# 04_SWITCH.net
KiCad netlist of a schematic drawn in Altium Designer
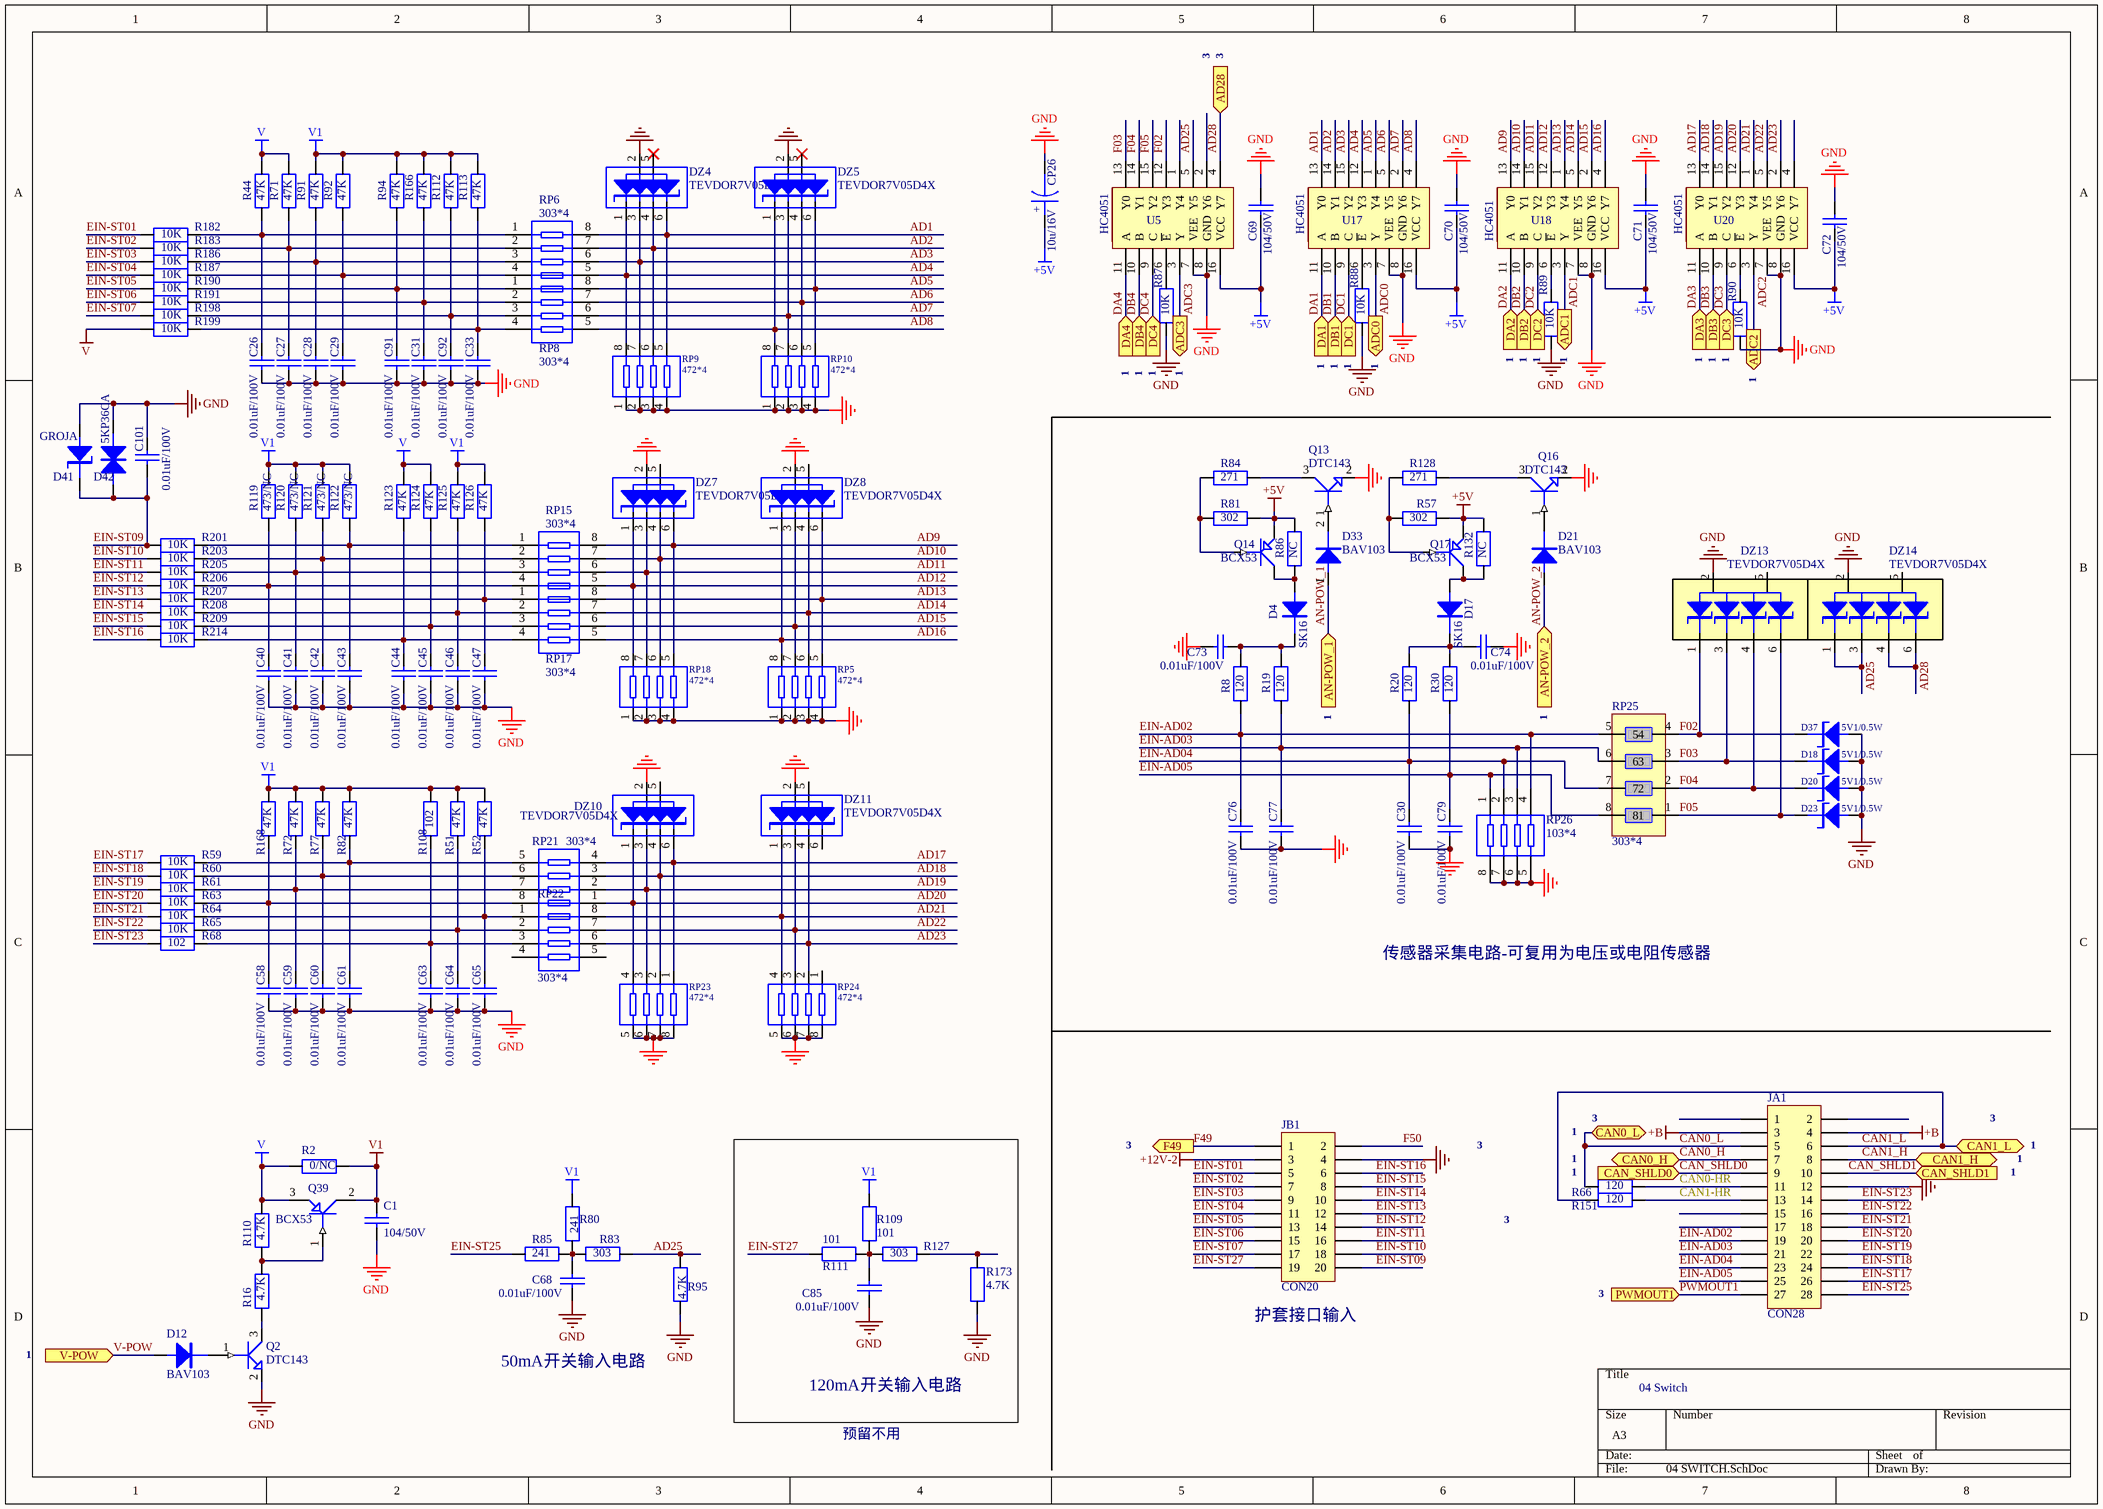
[diagram p0: 04 SWITCH.SchDoc]

(export (version "E")
  (design (tool "Eeschema 10.0.6"))
  (components
    (comp (ref "C1")
      (value "104/50V")
      (footprint "CR0805")
      (description "贴片电容")
      (libsource (lib "*") (part "CAP"))
    )
    (comp (ref "C26")
      (value "0.01uF/100V")
      (footprint "CR0805")
      (description "Capacitor")
      (libsource (lib "*") (part "CAP"))
    )
    (comp (ref "C27")
      (value "0.01uF/100V")
      (footprint "CR0805")
      (description "Capacitor")
      (libsource (lib "*") (part "CAP"))
    )
    (comp (ref "C28")
      (value "0.01uF/100V")
      (footprint "CR0805")
      (description "Capacitor")
      (libsource (lib "*") (part "CAP"))
    )
    (comp (ref "C29")
      (value "0.01uF/100V")
      (footprint "CR0805")
      (description "Capacitor")
      (libsource (lib "*") (part "CAP"))
    )
    (comp (ref "C30")
      (value "0.01uF/100V")
      (footprint "CR0805")
      (description "Capacitor")
      (libsource (lib "*") (part "CAP"))
    )
    (comp (ref "C31")
      (value "0.01uF/100V")
      (footprint "CR0805")
      (description "Capacitor")
      (libsource (lib "*") (part "CAP"))
    )
    (comp (ref "C33")
      (value "0.01uF/100V")
      (footprint "CR0805")
      (description "Capacitor")
      (libsource (lib "*") (part "CAP"))
    )
    (comp (ref "C40")
      (value "0.01uF/100V")
      (footprint "CR0805")
      (description "Capacitor")
      (libsource (lib "*") (part "CAP"))
    )
    (comp (ref "C41")
      (value "0.01uF/100V")
      (footprint "CR0805")
      (description "Capacitor")
      (libsource (lib "*") (part "CAP"))
    )
    (comp (ref "C42")
      (value "0.01uF/100V")
      (footprint "CR0805")
      (description "Capacitor")
      (libsource (lib "*") (part "CAP"))
    )
    (comp (ref "C43")
      (value "0.01uF/100V")
      (footprint "CR0805")
      (description "Capacitor")
      (libsource (lib "*") (part "CAP"))
    )
    (comp (ref "C44")
      (value "0.01uF/100V")
      (footprint "CR0805")
      (description "Capacitor")
      (libsource (lib "*") (part "CAP"))
    )
    (comp (ref "C45")
      (value "0.01uF/100V")
      (footprint "CR0805")
      (description "Capacitor")
      (libsource (lib "*") (part "CAP"))
    )
    (comp (ref "C46")
      (value "0.01uF/100V")
      (footprint "CR0805")
      (description "Capacitor")
      (libsource (lib "*") (part "CAP"))
    )
    (comp (ref "C47")
      (value "0.01uF/100V")
      (footprint "CR0805")
      (description "Capacitor")
      (libsource (lib "*") (part "CAP"))
    )
    (comp (ref "C58")
      (value "0.01uF/100V")
      (footprint "CR0805")
      (description "Capacitor")
      (libsource (lib "*") (part "CAP"))
    )
    (comp (ref "C59")
      (value "0.01uF/100V")
      (footprint "CR0805")
      (description "Capacitor")
      (libsource (lib "*") (part "CAP"))
    )
    (comp (ref "C60")
      (value "0.01uF/100V")
      (footprint "CR0805")
      (description "Capacitor")
      (libsource (lib "*") (part "CAP"))
    )
    (comp (ref "C61")
      (value "0.01uF/100V")
      (footprint "CR0805")
      (description "Capacitor")
      (libsource (lib "*") (part "CAP"))
    )
    (comp (ref "C63")
      (value "0.01uF/100V")
      (footprint "CR0805")
      (description "Capacitor")
      (libsource (lib "*") (part "CAP"))
    )
    (comp (ref "C64")
      (value "0.01uF/100V")
      (footprint "CR0805")
      (description "Capacitor")
      (libsource (lib "*") (part "CAP"))
    )
    (comp (ref "C65")
      (value "0.01uF/100V")
      (footprint "CR0805")
      (description "Capacitor")
      (libsource (lib "*") (part "CAP"))
    )
    (comp (ref "C68")
      (value "0.01uF/100V")
      (footprint "CR0805")
      (description "Capacitor")
      (libsource (lib "*") (part "CAP"))
    )
    (comp (ref "C69")
      (value "104/50V")
      (footprint "CR0805")
      (description "Capacitor")
      (libsource (lib "*") (part "CAP"))
    )
    (comp (ref "C70")
      (value "104/50V")
      (footprint "CR0805")
      (description "Capacitor")
      (libsource (lib "*") (part "CAP"))
    )
    (comp (ref "C71")
      (value "104/50V")
      (footprint "CR0805")
      (description "Capacitor")
      (libsource (lib "*") (part "CAP"))
    )
    (comp (ref "C72")
      (value "104/50V")
      (footprint "CR0805")
      (description "Capacitor")
      (libsource (lib "*") (part "CAP"))
    )
    (comp (ref "C73")
      (value "0.01uF/100V")
      (footprint "CR0805")
      (description "Capacitor")
      (libsource (lib "*") (part "CAP"))
    )
    (comp (ref "C74")
      (value "0.01uF/100V")
      (footprint "CR0805")
      (description "Capacitor")
      (libsource (lib "*") (part "CAP"))
    )
    (comp (ref "C76")
      (value "0.01uF/100V")
      (footprint "CR0805")
      (description "Capacitor")
      (libsource (lib "*") (part "CAP"))
    )
    (comp (ref "C77")
      (value "0.01uF/100V")
      (footprint "CR0805")
      (description "Capacitor")
      (libsource (lib "*") (part "CAP"))
    )
    (comp (ref "C79")
      (value "0.01uF/100V")
      (footprint "CR0805")
      (description "Capacitor")
      (libsource (lib "*") (part "CAP"))
    )
    (comp (ref "C85")
      (value "0.01uF/100V")
      (footprint "CR0805")
      (description "Capacitor")
      (libsource (lib "*") (part "CAP"))
    )
    (comp (ref "C91")
      (value "0.01uF/100V")
      (footprint "CR0805")
      (description "Capacitor")
      (libsource (lib "*") (part "CAP"))
    )
    (comp (ref "C92")
      (value "0.01uF/100V")
      (footprint "CR0805")
      (description "Capacitor")
      (libsource (lib "*") (part "CAP"))
    )
    (comp (ref "C101")
      (value "0.01uF/100V")
      (footprint "CR0805")
      (description "Capacitor")
      (libsource (lib "*") (part "CAP"))
    )
    (comp (ref "CP26")
      (value "10u/16V")
      (footprint "CE1206")
      (description "Capacitor")
      (libsource (lib "*") (part "CAPACITOR POL"))
    )
    (comp (ref "D4")
      (value "SK16")
      (footprint "SMA")
      (description "二极管")
      (libsource (lib "*") (part "DIODE"))
    )
    (comp (ref "D12")
      (value "BAV103")
      (footprint "SOD-80C")
      (description "二极管")
      (libsource (lib "*") (part "DIODE"))
    )
    (comp (ref "D17")
      (value "SK16")
      (footprint "SMA")
      (description "二极管")
      (libsource (lib "*") (part "DIODE"))
    )
    (comp (ref "D18")
      (value "5V1/0.5W")
      (footprint "SOD-80C")
      (description "稳压二极管")
      (libsource (lib "*") (part "DW"))
    )
    (comp (ref "D20")
      (value "5V1/0.5W")
      (footprint "SOD-80C")
      (description "稳压二极管")
      (libsource (lib "*") (part "DW"))
    )
    (comp (ref "D21")
      (value "BAV103")
      (footprint "SOD-80C")
      (description "二极管")
      (libsource (lib "*") (part "DIODE"))
    )
    (comp (ref "D23")
      (value "5V1/0.5W")
      (footprint "SOD-80C")
      (description "稳压二极管")
      (libsource (lib "*") (part "DW"))
    )
    (comp (ref "D33")
      (value "BAV103")
      (footprint "SOD-80C")
      (description "二极管")
      (libsource (lib "") (part "DIODE_1"))
    )
    (comp (ref "D37")
      (value "5V1/0.5W")
      (footprint "SOD-80C")
      (description "稳压二极管")
      (libsource (lib "*") (part "DW"))
    )
    (comp (ref "D41")
      (value "GROJA")
      (footprint "SMA")
      (description "稳压二极管")
      (libsource (lib "*") (part "DW"))
    )
    (comp (ref "D42") (value "5KP36CA") (footprint "SMB-D") (libsource (lib "*") (part "TVS")))
    (comp (ref "DZ4")
      (value "TEVDOR7V05D4X")
      (footprint "SOT-457")
      (description "二极管排")
      (libsource (lib "yibiaoschlib") (part "TEVDOR7V05D4X"))
    )
    (comp (ref "DZ5")
      (value "TEVDOR7V05D4X")
      (footprint "SOT-457")
      (description "二极管排")
      (libsource (lib "yibiaoschlib") (part "TEVDOR7V05D4X"))
    )
    (comp (ref "DZ7")
      (value "TEVDOR7V05D4X")
      (footprint "SOT-457")
      (description "二极管排")
      (libsource (lib "yibiaoschlib") (part "TEVDOR7V05D4X"))
    )
    (comp (ref "DZ8")
      (value "TEVDOR7V05D4X")
      (footprint "SOT-457")
      (description "二极管排")
      (libsource (lib "yibiaoschlib") (part "TEVDOR7V05D4X"))
    )
    (comp (ref "DZ10")
      (value "TEVDOR7V05D4X")
      (footprint "SOT-457")
      (description "二极管排")
      (libsource (lib "yibiaoschlib") (part "TEVDOR7V05D4X"))
    )
    (comp (ref "DZ11")
      (value "TEVDOR7V05D4X")
      (footprint "SOT-457")
      (description "二极管排")
      (libsource (lib "yibiaoschlib") (part "TEVDOR7V05D4X"))
    )
    (comp (ref "DZ13")
      (value "TEVDOR7V05D4X")
      (footprint "SOT-457")
      (description "二极管排")
      (libsource (lib "*") (part "TEVDOR7V05D4X"))
    )
    (comp (ref "DZ14")
      (value "TEVDOR7V05D4X")
      (footprint "SOT-457")
      (description "二极管排")
      (libsource (lib "*") (part "TEVDOR7V05D4X"))
    )
    (comp (ref "JA1") (value "CON28") (footprint "AMP DIP28") (libsource (lib "YDM-SQ-1SCH") (part "CON28")))
    (comp (ref "JB1") (value "CON20") (footprint "AMP DIP20") (libsource (lib "YDM-SQ-1SCH") (part "CON20")))
    (comp (ref "Q2")
      (value "DTC143")
      (footprint "SOT23")
      (description "NPN")
      (libsource (lib "Ô­ÀíÍ¼¿â-1SCH") (part "DTC143"))
    )
    (comp (ref "Q13")
      (value "DTC143")
      (footprint "SOT23")
      (description "NPN")
      (libsource (lib "Ô­ÀíÍ¼¿â-1SCH") (part "DTC143"))
    )
    (comp (ref "Q14")
      (value "BCX53")
      (footprint "SOT89")
      (description "贴片三极管")
      (libsource (lib "*") (part "PNP1"))
    )
    (comp (ref "Q16")
      (value "DTC143")
      (footprint "SOT23")
      (description "NPN")
      (libsource (lib "Ô­ÀíÍ¼¿â-1SCH") (part "DTC143"))
    )
    (comp (ref "Q17")
      (value "BCX53")
      (footprint "SOT89")
      (description "贴片三极管")
      (libsource (lib "*") (part "PNP1"))
    )
    (comp (ref "Q39")
      (value "BCX53")
      (footprint "SOT89")
      (description "PNP三极管")
      (libsource (lib "Ô­ÀíÍ¼¿â-1SCH") (part "BSP631"))
    )
    (comp (ref "R2")
      (value "0/NC")
      (footprint "CR1206")
      (description "贴片电阻")
      (libsource (lib "YDM-SQ-1SCH") (part "RES"))
    )
    (comp (ref "R8")
      (value "120")
      (footprint "CR1206")
      (description "贴片电阻")
      (libsource (lib "*") (part "RES"))
    )
    (comp (ref "R16")
      (value "4.7K")
      (footprint "CR1206")
      (description "贴片电阻")
      (libsource (lib "*") (part "RES"))
    )
    (comp (ref "R19")
      (value "120")
      (footprint "CR1206")
      (description "贴片电阻")
      (libsource (lib "*") (part "RES"))
    )
    (comp (ref "R20")
      (value "120")
      (footprint "CR1206")
      (description "贴片电阻")
      (libsource (lib "*") (part "RES"))
    )
    (comp (ref "R30")
      (value "120")
      (footprint "CR1206")
      (description "贴片电阻")
      (libsource (lib "*") (part "RES"))
    )
    (comp (ref "R44")
      (value "47K")
      (footprint "CR0805")
      (description "贴片电阻")
      (libsource (lib "*") (part "RES"))
    )
    (comp (ref "R51")
      (value "47K")
      (footprint "CR0805")
      (description "贴片电阻")
      (libsource (lib "*") (part "RES"))
    )
    (comp (ref "R52")
      (value "47K")
      (footprint "CR0805")
      (description "贴片电阻")
      (libsource (lib "*") (part "RES"))
    )
    (comp (ref "R57")
      (value "302")
      (footprint "CR0805")
      (description "贴片电阻")
      (libsource (lib "*") (part "RES"))
    )
    (comp (ref "R59")
      (value "10K")
      (footprint "CR1206")
      (description "贴片电阻")
      (libsource (lib "*") (part "RES"))
    )
    (comp (ref "R60")
      (value "10K")
      (footprint "CR1206")
      (description "贴片电阻")
      (libsource (lib "*") (part "RES"))
    )
    (comp (ref "R61")
      (value "10K")
      (footprint "CR1206")
      (description "贴片电阻")
      (libsource (lib "*") (part "RES"))
    )
    (comp (ref "R63")
      (value "10K")
      (footprint "CR1206")
      (description "贴片电阻")
      (libsource (lib "*") (part "RES"))
    )
    (comp (ref "R64")
      (value "10K")
      (footprint "CR1206")
      (description "贴片电阻")
      (libsource (lib "*") (part "RES"))
    )
    (comp (ref "R65")
      (value "10K")
      (footprint "CR1206")
      (description "贴片电阻")
      (libsource (lib "*") (part "RES"))
    )
    (comp (ref "R66")
      (value "120")
      (footprint "CR0805")
      (description "贴片电阻")
      (libsource (lib "*") (part "RES"))
    )
    (comp (ref "R68")
      (value "102")
      (footprint "CR2010")
      (description "贴片电阻")
      (libsource (lib "*") (part "RES"))
    )
    (comp (ref "R71")
      (value "47K")
      (footprint "CR0805")
      (description "贴片电阻")
      (libsource (lib "*") (part "RES"))
    )
    (comp (ref "R72")
      (value "47K")
      (footprint "CR0805")
      (description "贴片电阻")
      (libsource (lib "*") (part "RES"))
    )
    (comp (ref "R77")
      (value "47K")
      (footprint "CR0805")
      (description "贴片电阻")
      (libsource (lib "*") (part "RES"))
    )
    (comp (ref "R80")
      (value "241")
      (footprint "R-3W")
      (description "贴片电阻")
      (libsource (lib "*") (part "RES"))
    )
    (comp (ref "R81")
      (value "302")
      (footprint "CR0805")
      (description "贴片电阻")
      (libsource (lib "*") (part "RES"))
    )
    (comp (ref "R82")
      (value "47K")
      (footprint "CR0805")
      (description "贴片电阻")
      (libsource (lib "*") (part "RES"))
    )
    (comp (ref "R83")
      (value "303")
      (footprint "CR0805")
      (description "贴片电阻")
      (libsource (lib "*") (part "RES"))
    )
    (comp (ref "R84")
      (value "271")
      (footprint "CR0805")
      (description "贴片电阻")
      (libsource (lib "*") (part "RES"))
    )
    (comp (ref "R85")
      (value "241")
      (footprint "R-3W")
      (description "贴片电阻")
      (libsource (lib "*") (part "RES"))
    )
    (comp (ref "R86")
      (value "NC")
      (footprint "CR1206")
      (description "贴片电阻")
      (libsource (lib "*") (part "RES"))
    )
    (comp (ref "R87")
      (value "10K")
      (footprint "CR0805")
      (description "贴片电阻")
      (libsource (lib "*") (part "RES"))
    )
    (comp (ref "R88")
      (value "10K")
      (footprint "CR0805")
      (description "贴片电阻")
      (libsource (lib "*") (part "RES"))
    )
    (comp (ref "R89")
      (value "10K")
      (footprint "CR0805")
      (description "贴片电阻")
      (libsource (lib "*") (part "RES"))
    )
    (comp (ref "R90")
      (value "10K")
      (footprint "CR0805")
      (description "贴片电阻")
      (libsource (lib "*") (part "RES"))
    )
    (comp (ref "R91")
      (value "47K")
      (footprint "CR0805")
      (description "贴片电阻")
      (libsource (lib "*") (part "RES"))
    )
    (comp (ref "R92")
      (value "47K")
      (footprint "CR0805")
      (description "贴片电阻")
      (libsource (lib "*") (part "RES"))
    )
    (comp (ref "R94")
      (value "47K")
      (footprint "CR0805")
      (description "贴片电阻")
      (libsource (lib "*") (part "RES"))
    )
    (comp (ref "R95")
      (value "4.7K")
      (footprint "CR0805")
      (description "贴片电阻")
      (libsource (lib "*") (part "RES"))
    )
    (comp (ref "R108")
      (value "102")
      (footprint "CR2010")
      (description "贴片电阻")
      (libsource (lib "*") (part "RES"))
    )
    (comp (ref "R109")
      (value "101")
      (footprint "R-3W")
      (description "贴片电阻")
      (libsource (lib "*") (part "RES"))
    )
    (comp (ref "R110")
      (value "4.7K")
      (footprint "CR0805")
      (description "贴片电阻")
      (libsource (lib "*") (part "RES"))
    )
    (comp (ref "R111")
      (value "101")
      (footprint "R-3W")
      (description "贴片电阻")
      (libsource (lib "*") (part "RES"))
    )
    (comp (ref "R112")
      (value "47K")
      (footprint "CR0805")
      (description "贴片电阻")
      (libsource (lib "*") (part "RES"))
    )
    (comp (ref "R113")
      (value "47K")
      (footprint "CR0805")
      (description "贴片电阻")
      (libsource (lib "*") (part "RES"))
    )
    (comp (ref "R119")
      (value "473/NC")
      (footprint "CR0805")
      (description "贴片电阻")
      (libsource (lib "*") (part "RES"))
    )
    (comp (ref "R120")
      (value "473/NC")
      (footprint "CR0805")
      (description "贴片电阻")
      (libsource (lib "*") (part "RES"))
    )
    (comp (ref "R121")
      (value "473/NC")
      (footprint "CR0805")
      (description "贴片电阻")
      (libsource (lib "*") (part "RES"))
    )
    (comp (ref "R122")
      (value "473/NC")
      (footprint "CR0805")
      (description "贴片电阻")
      (libsource (lib "*") (part "RES"))
    )
    (comp (ref "R123")
      (value "47K")
      (footprint "CR0805")
      (description "贴片电阻")
      (libsource (lib "*") (part "RES"))
    )
    (comp (ref "R124")
      (value "47K")
      (footprint "CR0805")
      (description "贴片电阻")
      (libsource (lib "*") (part "RES"))
    )
    (comp (ref "R125")
      (value "47K")
      (footprint "CR0805")
      (description "贴片电阻")
      (libsource (lib "*") (part "RES"))
    )
    (comp (ref "R126")
      (value "47K")
      (footprint "CR0805")
      (description "贴片电阻")
      (libsource (lib "*") (part "RES"))
    )
    (comp (ref "R127")
      (value "303")
      (footprint "CR0805")
      (description "贴片电阻")
      (libsource (lib "*") (part "RES"))
    )
    (comp (ref "R128")
      (value "271")
      (footprint "CR0805")
      (description "贴片电阻")
      (libsource (lib "*") (part "RES"))
    )
    (comp (ref "R132")
      (value "NC")
      (footprint "CR1206")
      (description "贴片电阻")
      (libsource (lib "*") (part "RES"))
    )
    (comp (ref "R151")
      (value "120")
      (footprint "CR0805")
      (description "贴片电阻")
      (libsource (lib "*") (part "RES"))
    )
    (comp (ref "R166")
      (value "47K")
      (footprint "CR0805")
      (description "贴片电阻")
      (libsource (lib "*") (part "RES"))
    )
    (comp (ref "R168")
      (value "47K")
      (footprint "CR0805")
      (description "贴片电阻")
      (libsource (lib "*") (part "RES"))
    )
    (comp (ref "R173")
      (value "4.7K")
      (footprint "CR0805")
      (description "贴片电阻")
      (libsource (lib "*") (part "RES"))
    )
    (comp (ref "R182")
      (value "10K")
      (footprint "CR1206")
      (description "贴片电阻")
      (libsource (lib "*") (part "RES"))
    )
    (comp (ref "R183")
      (value "10K")
      (footprint "CR1206")
      (description "贴片电阻")
      (libsource (lib "*") (part "RES"))
    )
    (comp (ref "R186")
      (value "10K")
      (footprint "CR1206")
      (description "贴片电阻")
      (libsource (lib "*") (part "RES"))
    )
    (comp (ref "R187")
      (value "10K")
      (footprint "CR1206")
      (description "贴片电阻")
      (libsource (lib "*") (part "RES"))
    )
    (comp (ref "R190")
      (value "10K")
      (footprint "CR1206")
      (description "贴片电阻")
      (libsource (lib "*") (part "RES"))
    )
    (comp (ref "R191")
      (value "10K")
      (footprint "CR1206")
      (description "贴片电阻")
      (libsource (lib "*") (part "RES"))
    )
    (comp (ref "R198")
      (value "10K")
      (footprint "CR1206")
      (description "贴片电阻")
      (libsource (lib "*") (part "RES"))
    )
    (comp (ref "R199")
      (value "10K")
      (footprint "CR1206")
      (description "贴片电阻")
      (libsource (lib "*") (part "RES"))
    )
    (comp (ref "R201")
      (value "10K")
      (footprint "CR1206")
      (description "贴片电阻")
      (libsource (lib "*") (part "RES"))
    )
    (comp (ref "R203")
      (value "10K")
      (footprint "CR1206")
      (description "贴片电阻")
      (libsource (lib "*") (part "RES"))
    )
    (comp (ref "R205")
      (value "10K")
      (footprint "CR1206")
      (description "贴片电阻")
      (libsource (lib "*") (part "RES"))
    )
    (comp (ref "R206")
      (value "10K")
      (footprint "CR1206")
      (description "贴片电阻")
      (libsource (lib "*") (part "RES"))
    )
    (comp (ref "R207")
      (value "10K")
      (footprint "CR1206")
      (description "贴片电阻")
      (libsource (lib "*") (part "RES"))
    )
    (comp (ref "R208")
      (value "10K")
      (footprint "CR1206")
      (description "贴片电阻")
      (libsource (lib "*") (part "RES"))
    )
    (comp (ref "R209")
      (value "10K")
      (footprint "CR1206")
      (description "贴片电阻")
      (libsource (lib "*") (part "RES"))
    )
    (comp (ref "R214")
      (value "10K")
      (footprint "CR1206")
      (description "贴片电阻")
      (libsource (lib "*") (part "RES"))
    )
    (comp (ref "RP5")
      (value "472*4")
      (footprint "R4")
      (description "排阻")
      (libsource (lib "yibiaoschlib") (part "RN"))
    )
    (comp (ref "RP6")
      (value "303*4")
      (footprint "R4")
      (description "贴片排阻")
      (libsource (lib "*") (part "R_LINE4"))
    )
    (comp (ref "RP8")
      (value "303*4")
      (footprint "R4")
      (description "贴片排阻")
      (libsource (lib "*") (part "R_LINE4"))
    )
    (comp (ref "RP9")
      (value "472*4")
      (footprint "R4")
      (description "排阻")
      (libsource (lib "yibiaoschlib") (part "RN"))
    )
    (comp (ref "RP10")
      (value "472*4")
      (footprint "R4")
      (description "排阻")
      (libsource (lib "yibiaoschlib") (part "RN"))
    )
    (comp (ref "RP15")
      (value "303*4")
      (footprint "R4")
      (description "贴片排阻")
      (libsource (lib "*") (part "R_LINE4"))
    )
    (comp (ref "RP17")
      (value "303*4")
      (footprint "R4")
      (description "贴片排阻")
      (libsource (lib "*") (part "R_LINE4"))
    )
    (comp (ref "RP18")
      (value "472*4")
      (footprint "R4")
      (description "排阻")
      (libsource (lib "yibiaoschlib") (part "RN"))
    )
    (comp (ref "RP21")
      (value "303*4")
      (footprint "R4")
      (description "贴片排阻")
      (libsource (lib "*") (part "R_LINE4"))
    )
    (comp (ref "RP22")
      (value "303*4")
      (footprint "R4")
      (description "贴片排阻")
      (libsource (lib "*") (part "R_LINE4"))
    )
    (comp (ref "RP23")
      (value "472*4")
      (footprint "R4")
      (description "排阻")
      (libsource (lib "yibiaoschlib") (part "RN"))
    )
    (comp (ref "RP24")
      (value "472*4")
      (footprint "R4")
      (description "排阻")
      (libsource (lib "yibiaoschlib") (part "RN"))
    )
    (comp (ref "RP25") (value "303*4") (footprint "R4") (libsource (lib "*") (part "R_ARRAY")))
    (comp (ref "RP26")
      (value "103*4")
      (footprint "R4")
      (description "排阻")
      (libsource (lib "*") (part "R_LINE4"))
    )
    (comp (ref "U5")
      (value "HC4051")
      (footprint "SO-16")
      (description "IC-8路模拟开关集成快")
      (libsource (lib "YDM-SQ-1SCH") (part "HC4051"))
    )
    (comp (ref "U17")
      (value "HC4051")
      (footprint "SO-16")
      (description "IC-8路模拟开关集成快")
      (libsource (lib "YDM-SQ-1SCH") (part "HC4051"))
    )
    (comp (ref "U18")
      (value "HC4051")
      (footprint "SO-16")
      (description "IC-8路模拟开关集成快")
      (libsource (lib "YDM-SQ-1SCH") (part "HC4051"))
    )
    (comp (ref "U20")
      (value "HC4051")
      (footprint "SO-16")
      (description "IC-8路模拟开关集成快")
      (libsource (lib "YDM-SQ-1SCH") (part "HC4051"))
    )
  )
  (nets
    (net (code "1") (name "+5V") (class "Default")
      (node (ref "C69") (pin "2") (pinfunction "2_2") (pintype "passive"))
      (node (ref "C70") (pin "2") (pinfunction "2_2") (pintype "passive"))
      (node (ref "C71") (pin "2") (pinfunction "2_2") (pintype "passive"))
      (node (ref "C72") (pin "2") (pinfunction "2_2") (pintype "passive"))
      (node (ref "CP26") (pin "1") (pinfunction "1_1") (pintype "passive"))
      (node (ref "Q14") (pin "3") (pinfunction "E_3") (pintype "passive"))
      (node (ref "Q17") (pin "3") (pinfunction "E_3") (pintype "passive"))
      (node (ref "R132") (pin "1") (pinfunction "1_1") (pintype "passive"))
      (node (ref "R57") (pin "1") (pinfunction "1_1") (pintype "passive"))
      (node (ref "R81") (pin "1") (pinfunction "1_1") (pintype "passive"))
      (node (ref "R86") (pin "1") (pinfunction "1_1") (pintype "passive"))
      (node (ref "U17") (pin "16") (pinfunction "VCC_16") (pintype "passive"))
      (node (ref "U18") (pin "16") (pinfunction "VCC_16") (pintype "passive"))
      (node (ref "U20") (pin "16") (pinfunction "VCC_16") (pintype "passive"))
      (node (ref "U5") (pin "16") (pinfunction "VCC_16") (pintype "passive"))
    )
    (net (code "2") (name "+12V-2") (class "Default")
      (node (ref "JB1") (pin "3") (pinfunction "3_3") (pintype "passive"))
    )
    (net (code "3") (name "+B") (class "Default")
      (node (ref "JA1") (pin "3") (pinfunction "3_3") (pintype "passive"))
      (node (ref "JA1") (pin "4") (pinfunction "4_4") (pintype "passive"))
    )
    (net (code "4") (name "/AD1") (class "Default")
      (node (ref "DZ4") (pin "6") (pintype "passive"))
      (node (ref "RP6") (pin "8") (pinfunction "8_8") (pintype "passive"))
      (node (ref "RP9") (pin "5") (pinfunction "5_5") (pintype "passive"))
      (node (ref "U17") (pin "13") (pinfunction "Y0_13") (pintype "passive"))
    )
    (net (code "5") (name "/AD2") (class "Default")
      (node (ref "DZ4") (pin "4") (pintype "passive"))
      (node (ref "RP6") (pin "7") (pinfunction "7_7") (pintype "passive"))
      (node (ref "RP9") (pin "6") (pinfunction "6_6") (pintype "passive"))
      (node (ref "U17") (pin "14") (pinfunction "Y1_14") (pintype "passive"))
    )
    (net (code "6") (name "/AD3") (class "Default")
      (node (ref "DZ4") (pin "3") (pintype "passive"))
      (node (ref "RP6") (pin "6") (pinfunction "6_6") (pintype "passive"))
      (node (ref "RP9") (pin "7") (pinfunction "7_7") (pintype "passive"))
      (node (ref "U17") (pin "15") (pinfunction "Y2_15") (pintype "passive"))
    )
    (net (code "7") (name "/AD4") (class "Default")
      (node (ref "DZ4") (pin "1") (pintype "passive"))
      (node (ref "RP6") (pin "5") (pinfunction "5_5") (pintype "passive"))
      (node (ref "RP9") (pin "8") (pinfunction "8_8") (pintype "passive"))
      (node (ref "U17") (pin "12") (pinfunction "Y3_12") (pintype "passive"))
    )
    (net (code "8") (name "/AD5") (class "Default")
      (node (ref "DZ5") (pin "6") (pintype "passive"))
      (node (ref "RP10") (pin "5") (pinfunction "5_5") (pintype "passive"))
      (node (ref "RP8") (pin "8") (pinfunction "8_8") (pintype "passive"))
      (node (ref "U17") (pin "1") (pinfunction "Y4_1") (pintype "passive"))
    )
    (net (code "9") (name "/AD6") (class "Default")
      (node (ref "DZ5") (pin "4") (pintype "passive"))
      (node (ref "RP10") (pin "6") (pinfunction "6_6") (pintype "passive"))
      (node (ref "RP8") (pin "7") (pinfunction "7_7") (pintype "passive"))
      (node (ref "U17") (pin "5") (pinfunction "Y5_5") (pintype "passive"))
    )
    (net (code "10") (name "/AD7") (class "Default")
      (node (ref "DZ5") (pin "3") (pintype "passive"))
      (node (ref "RP10") (pin "7") (pinfunction "7_7") (pintype "passive"))
      (node (ref "RP8") (pin "6") (pinfunction "6_6") (pintype "passive"))
      (node (ref "U17") (pin "2") (pinfunction "Y6_2") (pintype "passive"))
    )
    (net (code "11") (name "/AD8") (class "Default")
      (node (ref "DZ5") (pin "1") (pintype "passive"))
      (node (ref "RP10") (pin "8") (pinfunction "8_8") (pintype "passive"))
      (node (ref "RP8") (pin "5") (pinfunction "5_5") (pintype "passive"))
      (node (ref "U17") (pin "4") (pinfunction "Y7_4") (pintype "passive"))
    )
    (net (code "12") (name "/AD9") (class "Default")
      (node (ref "DZ7") (pin "6") (pintype "passive"))
      (node (ref "RP15") (pin "8") (pinfunction "8_8") (pintype "passive"))
      (node (ref "RP18") (pin "5") (pinfunction "5_5") (pintype "passive"))
      (node (ref "U18") (pin "13") (pinfunction "Y0_13") (pintype "passive"))
    )
    (net (code "13") (name "/AD10") (class "Default")
      (node (ref "DZ7") (pin "4") (pintype "passive"))
      (node (ref "RP15") (pin "7") (pinfunction "7_7") (pintype "passive"))
      (node (ref "RP18") (pin "6") (pinfunction "6_6") (pintype "passive"))
      (node (ref "U18") (pin "14") (pinfunction "Y1_14") (pintype "passive"))
    )
    (net (code "14") (name "/AD11") (class "Default")
      (node (ref "DZ7") (pin "3") (pintype "passive"))
      (node (ref "RP15") (pin "6") (pinfunction "6_6") (pintype "passive"))
      (node (ref "RP18") (pin "7") (pinfunction "7_7") (pintype "passive"))
      (node (ref "U18") (pin "15") (pinfunction "Y2_15") (pintype "passive"))
    )
    (net (code "15") (name "/AD12") (class "Default")
      (node (ref "DZ7") (pin "1") (pintype "passive"))
      (node (ref "RP15") (pin "5") (pinfunction "5_5") (pintype "passive"))
      (node (ref "RP18") (pin "8") (pinfunction "8_8") (pintype "passive"))
      (node (ref "U18") (pin "12") (pinfunction "Y3_12") (pintype "passive"))
    )
    (net (code "16") (name "/AD13") (class "Default")
      (node (ref "DZ8") (pin "6") (pintype "passive"))
      (node (ref "RP17") (pin "8") (pinfunction "8_8") (pintype "passive"))
      (node (ref "RP5") (pin "5") (pinfunction "5_5") (pintype "passive"))
      (node (ref "U18") (pin "1") (pinfunction "Y4_1") (pintype "passive"))
    )
    (net (code "17") (name "/AD14") (class "Default")
      (node (ref "DZ8") (pin "4") (pintype "passive"))
      (node (ref "RP17") (pin "7") (pinfunction "7_7") (pintype "passive"))
      (node (ref "RP5") (pin "6") (pinfunction "6_6") (pintype "passive"))
      (node (ref "U18") (pin "5") (pinfunction "Y5_5") (pintype "passive"))
    )
    (net (code "18") (name "/AD15") (class "Default")
      (node (ref "DZ8") (pin "3") (pintype "passive"))
      (node (ref "RP17") (pin "6") (pinfunction "6_6") (pintype "passive"))
      (node (ref "RP5") (pin "7") (pinfunction "7_7") (pintype "passive"))
      (node (ref "U18") (pin "2") (pinfunction "Y6_2") (pintype "passive"))
    )
    (net (code "19") (name "/AD16") (class "Default")
      (node (ref "DZ8") (pin "1") (pintype "passive"))
      (node (ref "RP17") (pin "5") (pinfunction "5_5") (pintype "passive"))
      (node (ref "RP5") (pin "8") (pinfunction "8_8") (pintype "passive"))
      (node (ref "U18") (pin "4") (pinfunction "Y7_4") (pintype "passive"))
    )
    (net (code "20") (name "/AD17") (class "Default")
      (node (ref "DZ10") (pin "6") (pintype "passive"))
      (node (ref "RP21") (pin "4") (pinfunction "4_4") (pintype "passive"))
      (node (ref "RP23") (pin "1") (pinfunction "1_1") (pintype "passive"))
      (node (ref "U20") (pin "13") (pinfunction "Y0_13") (pintype "passive"))
    )
    (net (code "21") (name "/AD18") (class "Default")
      (node (ref "DZ10") (pin "4") (pintype "passive"))
      (node (ref "RP21") (pin "3") (pinfunction "3_3") (pintype "passive"))
      (node (ref "RP23") (pin "2") (pinfunction "2_2") (pintype "passive"))
      (node (ref "U20") (pin "14") (pinfunction "Y1_14") (pintype "passive"))
    )
    (net (code "22") (name "/AD19") (class "Default")
      (node (ref "DZ10") (pin "3") (pintype "passive"))
      (node (ref "RP21") (pin "2") (pinfunction "2_2") (pintype "passive"))
      (node (ref "RP23") (pin "3") (pinfunction "3_3") (pintype "passive"))
      (node (ref "U20") (pin "15") (pinfunction "Y2_15") (pintype "passive"))
    )
    (net (code "23") (name "/AD20") (class "Default")
      (node (ref "DZ10") (pin "1") (pintype "passive"))
      (node (ref "RP21") (pin "1") (pinfunction "1_1") (pintype "passive"))
      (node (ref "RP23") (pin "4") (pinfunction "4_4") (pintype "passive"))
      (node (ref "U20") (pin "12") (pinfunction "Y3_12") (pintype "passive"))
    )
    (net (code "24") (name "/AD21") (class "Default")
      (node (ref "DZ11") (pin "1") (pintype "passive"))
      (node (ref "RP22") (pin "8") (pinfunction "8_8") (pintype "passive"))
      (node (ref "RP24") (pin "4") (pinfunction "4_4") (pintype "passive"))
      (node (ref "U20") (pin "1") (pinfunction "Y4_1") (pintype "passive"))
    )
    (net (code "25") (name "/AD22") (class "Default")
      (node (ref "DZ11") (pin "3") (pintype "passive"))
      (node (ref "RP22") (pin "7") (pinfunction "7_7") (pintype "passive"))
      (node (ref "RP24") (pin "3") (pinfunction "3_3") (pintype "passive"))
      (node (ref "U20") (pin "5") (pinfunction "Y5_5") (pintype "passive"))
    )
    (net (code "26") (name "/AD23") (class "Default")
      (node (ref "DZ11") (pin "4") (pintype "passive"))
      (node (ref "RP22") (pin "6") (pinfunction "6_6") (pintype "passive"))
      (node (ref "RP24") (pin "2") (pinfunction "2_2") (pintype "passive"))
      (node (ref "U20") (pin "2") (pinfunction "Y6_2") (pintype "passive"))
    )
    (net (code "27") (name "/AD25") (class "Default")
      (node (ref "DZ14") (pin "1") (pintype "passive"))
      (node (ref "DZ14") (pin "3") (pintype "passive"))
      (node (ref "R83") (pin "2") (pinfunction "2_2") (pintype "passive"))
      (node (ref "R95") (pin "2") (pinfunction "2_2") (pintype "passive"))
      (node (ref "U5") (pin "5") (pinfunction "Y5_5") (pintype "passive"))
    )
    (net (code "28") (name "/AD28") (class "Default")
      (node (ref "DZ14") (pin "4") (pintype "passive"))
      (node (ref "DZ14") (pin "6") (pintype "passive"))
      (node (ref "U5") (pin "4") (pinfunction "Y7_4") (pintype "passive"))
    )
    (net (code "29") (name "/ADC0") (class "Default")
      (node (ref "U17") (pin "3") (pinfunction "Y_3") (pintype "passive"))
    )
    (net (code "30") (name "/ADC1") (class "Default")
      (node (ref "U18") (pin "3") (pinfunction "Y_3") (pintype "passive"))
    )
    (net (code "31") (name "/ADC2") (class "Default")
      (node (ref "U20") (pin "3") (pinfunction "Y_3") (pintype "passive"))
    )
    (net (code "32") (name "/ADC3") (class "Default")
      (node (ref "U5") (pin "3") (pinfunction "Y_3") (pintype "passive"))
    )
    (net (code "33") (name "/AN-POW_1") (class "Default")
      (node (ref "D33") (pin "1") (pinfunction "A_1") (pintype "passive"))
    )
    (net (code "34") (name "/AN-POW_2") (class "Default")
      (node (ref "D21") (pin "1") (pinfunction "A_1") (pintype "passive"))
    )
    (net (code "35") (name "/CAN0-HR") (class "Default")
      (node (ref "JA1") (pin "11") (pinfunction "11_11") (pintype "passive"))
      (node (ref "R66") (pin "2") (pinfunction "2_2") (pintype "passive"))
    )
    (net (code "36") (name "/CAN0_H") (class "Default")
      (node (ref "JA1") (pin "7") (pinfunction "7_7") (pintype "passive"))
    )
    (net (code "37") (name "/CAN0_L") (class "Default")
      (node (ref "JA1") (pin "5") (pinfunction "5_5") (pintype "passive"))
      (node (ref "R66") (pin "1") (pinfunction "1_1") (pintype "passive"))
    )
    (net (code "38") (name "/CAN1-HR") (class "Default")
      (node (ref "JA1") (pin "13") (pinfunction "13_13") (pintype "passive"))
      (node (ref "R151") (pin "1") (pinfunction "1_1") (pintype "passive"))
    )
    (net (code "39") (name "/CAN1_H") (class "Default")
      (node (ref "JA1") (pin "8") (pinfunction "8_8") (pintype "passive"))
    )
    (net (code "40") (name "/CAN1_L") (class "Default")
      (node (ref "JA1") (pin "6") (pinfunction "6_6") (pintype "passive"))
      (node (ref "R151") (pin "2") (pinfunction "2_2") (pintype "passive"))
    )
    (net (code "41") (name "/CAN_SHLD0") (class "Default")
      (node (ref "JA1") (pin "9") (pinfunction "9_9") (pintype "passive"))
    )
    (net (code "42") (name "/CAN_SHLD1") (class "Default")
      (node (ref "JA1") (pin "10") (pinfunction "10_10") (pintype "passive"))
    )
    (net (code "43") (name "/DA1") (class "Default")
      (node (ref "U17") (pin "11") (pinfunction "A_11") (pintype "passive"))
    )
    (net (code "44") (name "/DA2") (class "Default")
      (node (ref "U18") (pin "11") (pinfunction "A_11") (pintype "passive"))
    )
    (net (code "45") (name "/DA3") (class "Default")
      (node (ref "U20") (pin "11") (pinfunction "A_11") (pintype "passive"))
    )
    (net (code "46") (name "/DA4") (class "Default")
      (node (ref "U5") (pin "11") (pinfunction "A_11") (pintype "passive"))
    )
    (net (code "47") (name "/DB1") (class "Default")
      (node (ref "U17") (pin "10") (pinfunction "B_10") (pintype "passive"))
    )
    (net (code "48") (name "/DB2") (class "Default")
      (node (ref "U18") (pin "10") (pinfunction "B_10") (pintype "passive"))
    )
    (net (code "49") (name "/DB3") (class "Default")
      (node (ref "U20") (pin "10") (pinfunction "B_10") (pintype "passive"))
    )
    (net (code "50") (name "/DB4") (class "Default")
      (node (ref "U5") (pin "10") (pinfunction "B_10") (pintype "passive"))
    )
    (net (code "51") (name "/DC1") (class "Default")
      (node (ref "U17") (pin "9") (pinfunction "C_9") (pintype "passive"))
    )
    (net (code "52") (name "/DC2") (class "Default")
      (node (ref "U18") (pin "9") (pinfunction "C_9") (pintype "passive"))
    )
    (net (code "53") (name "/DC3") (class "Default")
      (node (ref "U20") (pin "9") (pinfunction "C_9") (pintype "passive"))
    )
    (net (code "54") (name "/DC4") (class "Default")
      (node (ref "U5") (pin "9") (pinfunction "C_9") (pintype "passive"))
    )
    (net (code "55") (name "/EIN-AD02") (class "Default")
      (node (ref "C76") (pin "1") (pinfunction "1_1") (pintype "passive"))
      (node (ref "JA1") (pin "19") (pinfunction "19_19") (pintype "passive"))
      (node (ref "R8") (pin "2") (pinfunction "2_2") (pintype "passive"))
      (node (ref "RP25") (pin "5") (pinfunction "5_5") (pintype "passive"))
      (node (ref "RP26") (pin "4") (pinfunction "4_4") (pintype "passive"))
    )
    (net (code "56") (name "/EIN-AD03") (class "Default")
      (node (ref "C77") (pin "1") (pinfunction "1_1") (pintype "passive"))
      (node (ref "JA1") (pin "21") (pinfunction "21_21") (pintype "passive"))
      (node (ref "R19") (pin "2") (pinfunction "2_2") (pintype "passive"))
      (node (ref "RP25") (pin "6") (pinfunction "6_6") (pintype "passive"))
      (node (ref "RP26") (pin "3") (pinfunction "3_3") (pintype "passive"))
    )
    (net (code "57") (name "/EIN-AD04") (class "Default")
      (node (ref "C30") (pin "1") (pinfunction "1_1") (pintype "passive"))
      (node (ref "JA1") (pin "23") (pinfunction "23_23") (pintype "passive"))
      (node (ref "R20") (pin "2") (pinfunction "2_2") (pintype "passive"))
      (node (ref "RP25") (pin "7") (pinfunction "7_7") (pintype "passive"))
      (node (ref "RP26") (pin "2") (pinfunction "2_2") (pintype "passive"))
    )
    (net (code "58") (name "/EIN-AD05") (class "Default")
      (node (ref "C79") (pin "1") (pinfunction "1_1") (pintype "passive"))
      (node (ref "JA1") (pin "25") (pinfunction "25_25") (pintype "passive"))
      (node (ref "R30") (pin "2") (pinfunction "2_2") (pintype "passive"))
      (node (ref "RP25") (pin "8") (pinfunction "8_8") (pintype "passive"))
      (node (ref "RP26") (pin "1") (pinfunction "1_1") (pintype "passive"))
    )
    (net (code "59") (name "/EIN-ST01") (class "Default")
      (node (ref "JB1") (pin "5") (pinfunction "5_5") (pintype "passive"))
      (node (ref "R182") (pin "1") (pinfunction "1_1") (pintype "passive"))
    )
    (net (code "60") (name "/EIN-ST02") (class "Default")
      (node (ref "JB1") (pin "7") (pinfunction "7_7") (pintype "passive"))
      (node (ref "R183") (pin "1") (pinfunction "1_1") (pintype "passive"))
    )
    (net (code "61") (name "/EIN-ST03") (class "Default")
      (node (ref "JB1") (pin "9") (pinfunction "9_9") (pintype "passive"))
      (node (ref "R186") (pin "1") (pinfunction "1_1") (pintype "passive"))
    )
    (net (code "62") (name "/EIN-ST04") (class "Default")
      (node (ref "JB1") (pin "11") (pinfunction "11_11") (pintype "passive"))
      (node (ref "R187") (pin "1") (pinfunction "1_1") (pintype "passive"))
    )
    (net (code "63") (name "/EIN-ST05") (class "Default")
      (node (ref "JB1") (pin "13") (pinfunction "13_13") (pintype "passive"))
      (node (ref "R190") (pin "1") (pinfunction "1_1") (pintype "passive"))
    )
    (net (code "64") (name "/EIN-ST06") (class "Default")
      (node (ref "JB1") (pin "15") (pinfunction "15_15") (pintype "passive"))
      (node (ref "R191") (pin "1") (pinfunction "1_1") (pintype "passive"))
    )
    (net (code "65") (name "/EIN-ST07") (class "Default")
      (node (ref "JB1") (pin "17") (pinfunction "17_17") (pintype "passive"))
      (node (ref "R198") (pin "1") (pinfunction "1_1") (pintype "passive"))
    )
    (net (code "66") (name "/EIN-ST09") (class "Default")
      (node (ref "C101") (pin "2") (pinfunction "2_2") (pintype "passive"))
      (node (ref "D41") (pin "2") (pinfunction "K_2") (pintype "passive"))
      (node (ref "D42") (pin "2") (pinfunction "2_2") (pintype "passive"))
      (node (ref "JB1") (pin "20") (pinfunction "20_20") (pintype "passive"))
      (node (ref "R201") (pin "1") (pinfunction "1_1") (pintype "passive"))
    )
    (net (code "67") (name "/EIN-ST10") (class "Default")
      (node (ref "JB1") (pin "18") (pinfunction "18_18") (pintype "passive"))
      (node (ref "R203") (pin "1") (pinfunction "1_1") (pintype "passive"))
    )
    (net (code "68") (name "/EIN-ST11") (class "Default")
      (node (ref "JB1") (pin "16") (pinfunction "16_16") (pintype "passive"))
      (node (ref "R205") (pin "1") (pinfunction "1_1") (pintype "passive"))
    )
    (net (code "69") (name "/EIN-ST12") (class "Default")
      (node (ref "JB1") (pin "14") (pinfunction "14_14") (pintype "passive"))
      (node (ref "R206") (pin "1") (pinfunction "1_1") (pintype "passive"))
    )
    (net (code "70") (name "/EIN-ST13") (class "Default")
      (node (ref "JB1") (pin "12") (pinfunction "12_12") (pintype "passive"))
      (node (ref "R207") (pin "1") (pinfunction "1_1") (pintype "passive"))
    )
    (net (code "71") (name "/EIN-ST14") (class "Default")
      (node (ref "JB1") (pin "10") (pinfunction "10_10") (pintype "passive"))
      (node (ref "R208") (pin "1") (pinfunction "1_1") (pintype "passive"))
    )
    (net (code "72") (name "/EIN-ST15") (class "Default")
      (node (ref "JB1") (pin "8") (pinfunction "8_8") (pintype "passive"))
      (node (ref "R209") (pin "1") (pinfunction "1_1") (pintype "passive"))
    )
    (net (code "73") (name "/EIN-ST16") (class "Default")
      (node (ref "JB1") (pin "6") (pinfunction "6_6") (pintype "passive"))
      (node (ref "R214") (pin "1") (pinfunction "1_1") (pintype "passive"))
    )
    (net (code "74") (name "/EIN-ST17") (class "Default")
      (node (ref "JA1") (pin "26") (pinfunction "26_26") (pintype "passive"))
      (node (ref "R59") (pin "1") (pinfunction "1_1") (pintype "passive"))
    )
    (net (code "75") (name "/EIN-ST18") (class "Default")
      (node (ref "JA1") (pin "24") (pinfunction "24_24") (pintype "passive"))
      (node (ref "R60") (pin "1") (pinfunction "1_1") (pintype "passive"))
    )
    (net (code "76") (name "/EIN-ST19") (class "Default")
      (node (ref "JA1") (pin "22") (pinfunction "22_22") (pintype "passive"))
      (node (ref "R61") (pin "1") (pinfunction "1_1") (pintype "passive"))
    )
    (net (code "77") (name "/EIN-ST20") (class "Default")
      (node (ref "JA1") (pin "20") (pinfunction "20_20") (pintype "passive"))
      (node (ref "R63") (pin "1") (pinfunction "1_1") (pintype "passive"))
    )
    (net (code "78") (name "/EIN-ST21") (class "Default")
      (node (ref "JA1") (pin "18") (pinfunction "18_18") (pintype "passive"))
      (node (ref "R64") (pin "1") (pinfunction "1_1") (pintype "passive"))
    )
    (net (code "79") (name "/EIN-ST22") (class "Default")
      (node (ref "JA1") (pin "16") (pinfunction "16_16") (pintype "passive"))
      (node (ref "R65") (pin "1") (pinfunction "1_1") (pintype "passive"))
    )
    (net (code "80") (name "/EIN-ST23") (class "Default")
      (node (ref "JA1") (pin "14") (pinfunction "14_14") (pintype "passive"))
      (node (ref "R68") (pin "1") (pinfunction "1_1") (pintype "passive"))
    )
    (net (code "81") (name "/EIN-ST25") (class "Default")
      (node (ref "JA1") (pin "28") (pinfunction "28_28") (pintype "passive"))
      (node (ref "R85") (pin "1") (pinfunction "1_1") (pintype "passive"))
    )
    (net (code "82") (name "/EIN-ST27") (class "Default")
      (node (ref "JB1") (pin "19") (pinfunction "19_19") (pintype "passive"))
      (node (ref "R111") (pin "1") (pinfunction "1_1") (pintype "passive"))
    )
    (net (code "83") (name "/F02") (class "Default")
      (node (ref "D37") (pin "2") (pinfunction "K_2") (pintype "passive"))
      (node (ref "DZ13") (pin "1") (pintype "passive"))
      (node (ref "RP25") (pin "4") (pinfunction "4_4") (pintype "passive"))
      (node (ref "U5") (pin "12") (pinfunction "Y3_12") (pintype "passive"))
    )
    (net (code "84") (name "/F03") (class "Default")
      (node (ref "D18") (pin "2") (pinfunction "K_2") (pintype "passive"))
      (node (ref "DZ13") (pin "3") (pintype "passive"))
      (node (ref "RP25") (pin "3") (pinfunction "3_3") (pintype "passive"))
      (node (ref "U5") (pin "13") (pinfunction "Y0_13") (pintype "passive"))
    )
    (net (code "85") (name "/F04") (class "Default")
      (node (ref "D20") (pin "2") (pinfunction "K_2") (pintype "passive"))
      (node (ref "DZ13") (pin "4") (pintype "passive"))
      (node (ref "RP25") (pin "2") (pinfunction "2_2") (pintype "passive"))
      (node (ref "U5") (pin "14") (pinfunction "Y1_14") (pintype "passive"))
    )
    (net (code "86") (name "/F05") (class "Default")
      (node (ref "D23") (pin "2") (pinfunction "K_2") (pintype "passive"))
      (node (ref "DZ13") (pin "6") (pintype "passive"))
      (node (ref "RP25") (pin "1") (pinfunction "1_1") (pintype "passive"))
      (node (ref "U5") (pin "15") (pinfunction "Y2_15") (pintype "passive"))
    )
    (net (code "87") (name "/F49") (class "Default")
      (node (ref "JB1") (pin "1") (pinfunction "1_1") (pintype "passive"))
    )
    (net (code "88") (name "/F50") (class "Default")
      (node (ref "JB1") (pin "2") (pinfunction "2_2") (pintype "passive"))
    )
    (net (code "89") (name "/PWMOUT1") (class "Default")
      (node (ref "JA1") (pin "27") (pinfunction "27_27") (pintype "passive"))
    )
    (net (code "90") (name "/V-POW") (class "Default")
      (node (ref "D12") (pin "1") (pinfunction "A_1") (pintype "passive"))
    )
    (net (code "91") (name "GND") (class "Default")
      (node (ref "C1") (pin "2") (pinfunction "2_2") (pintype "passive"))
      (node (ref "C101") (pin "1") (pinfunction "1_1") (pintype "passive"))
      (node (ref "C26") (pin "2") (pinfunction "2_2") (pintype "passive"))
      (node (ref "C27") (pin "2") (pinfunction "2_2") (pintype "passive"))
      (node (ref "C28") (pin "2") (pinfunction "2_2") (pintype "passive"))
      (node (ref "C29") (pin "2") (pinfunction "2_2") (pintype "passive"))
      (node (ref "C30") (pin "2") (pinfunction "2_2") (pintype "passive"))
      (node (ref "C31") (pin "2") (pinfunction "2_2") (pintype "passive"))
      (node (ref "C33") (pin "2") (pinfunction "2_2") (pintype "passive"))
      (node (ref "C40") (pin "2") (pinfunction "2_2") (pintype "passive"))
      (node (ref "C41") (pin "2") (pinfunction "2_2") (pintype "passive"))
      (node (ref "C42") (pin "2") (pinfunction "2_2") (pintype "passive"))
      (node (ref "C43") (pin "2") (pinfunction "2_2") (pintype "passive"))
      (node (ref "C44") (pin "2") (pinfunction "2_2") (pintype "passive"))
      (node (ref "C45") (pin "2") (pinfunction "2_2") (pintype "passive"))
      (node (ref "C46") (pin "2") (pinfunction "2_2") (pintype "passive"))
      (node (ref "C47") (pin "2") (pinfunction "2_2") (pintype "passive"))
      (node (ref "C58") (pin "2") (pinfunction "2_2") (pintype "passive"))
      (node (ref "C59") (pin "2") (pinfunction "2_2") (pintype "passive"))
      (node (ref "C60") (pin "2") (pinfunction "2_2") (pintype "passive"))
      (node (ref "C61") (pin "2") (pinfunction "2_2") (pintype "passive"))
      (node (ref "C63") (pin "2") (pinfunction "2_2") (pintype "passive"))
      (node (ref "C64") (pin "2") (pinfunction "2_2") (pintype "passive"))
      (node (ref "C65") (pin "2") (pinfunction "2_2") (pintype "passive"))
      (node (ref "C68") (pin "2") (pinfunction "2_2") (pintype "passive"))
      (node (ref "C69") (pin "1") (pinfunction "1_1") (pintype "passive"))
      (node (ref "C70") (pin "1") (pinfunction "1_1") (pintype "passive"))
      (node (ref "C71") (pin "1") (pinfunction "1_1") (pintype "passive"))
      (node (ref "C72") (pin "1") (pinfunction "1_1") (pintype "passive"))
      (node (ref "C73") (pin "1") (pinfunction "1_1") (pintype "passive"))
      (node (ref "C74") (pin "2") (pinfunction "2_2") (pintype "passive"))
      (node (ref "C76") (pin "2") (pinfunction "2_2") (pintype "passive"))
      (node (ref "C77") (pin "2") (pinfunction "2_2") (pintype "passive"))
      (node (ref "C79") (pin "2") (pinfunction "2_2") (pintype "passive"))
      (node (ref "C85") (pin "2") (pinfunction "2_2") (pintype "passive"))
      (node (ref "C91") (pin "2") (pinfunction "2_2") (pintype "passive"))
      (node (ref "C92") (pin "2") (pinfunction "2_2") (pintype "passive"))
      (node (ref "CP26") (pin "2") (pinfunction "2_2") (pintype "passive"))
      (node (ref "D18") (pin "1") (pinfunction "A_1") (pintype "passive"))
      (node (ref "D20") (pin "1") (pinfunction "A_1") (pintype "passive"))
      (node (ref "D23") (pin "1") (pinfunction "A_1") (pintype "passive"))
      (node (ref "D37") (pin "1") (pinfunction "A_1") (pintype "passive"))
      (node (ref "D41") (pin "1") (pinfunction "A_1") (pintype "passive"))
      (node (ref "D42") (pin "1") (pinfunction "1_1") (pintype "passive"))
      (node (ref "DZ10") (pin "2") (pintype "passive"))
      (node (ref "DZ11") (pin "2") (pintype "passive"))
      (node (ref "DZ13") (pin "2") (pintype "passive"))
      (node (ref "DZ14") (pin "2") (pintype "passive"))
      (node (ref "DZ4") (pin "2") (pintype "passive"))
      (node (ref "DZ5") (pin "2") (pintype "passive"))
      (node (ref "DZ7") (pin "2") (pintype "passive"))
      (node (ref "DZ8") (pin "2") (pintype "passive"))
      (node (ref "JA1") (pin "12") (pinfunction "12_12") (pintype "passive"))
      (node (ref "JB1") (pin "4") (pinfunction "4_4") (pintype "passive"))
      (node (ref "Q13") (pin "2") (pinfunction "gnd_2") (pintype "passive"))
      (node (ref "Q16") (pin "2") (pinfunction "gnd_2") (pintype "passive"))
      (node (ref "Q2") (pin "2") (pinfunction "gnd_2") (pintype "passive"))
      (node (ref "R173") (pin "1") (pinfunction "1_1") (pintype "passive"))
      (node (ref "R87") (pin "2") (pinfunction "2_2") (pintype "passive"))
      (node (ref "R88") (pin "2") (pinfunction "2_2") (pintype "passive"))
      (node (ref "R89") (pin "2") (pinfunction "2_2") (pintype "passive"))
      (node (ref "R90") (pin "2") (pinfunction "2_2") (pintype "passive"))
      (node (ref "R95") (pin "1") (pinfunction "1_1") (pintype "passive"))
      (node (ref "RP10") (pin "1") (pinfunction "1_1") (pintype "passive"))
      (node (ref "RP10") (pin "2") (pinfunction "2_2") (pintype "passive"))
      (node (ref "RP10") (pin "3") (pinfunction "3_3") (pintype "passive"))
      (node (ref "RP10") (pin "4") (pinfunction "4_4") (pintype "passive"))
      (node (ref "RP18") (pin "1") (pinfunction "1_1") (pintype "passive"))
      (node (ref "RP18") (pin "2") (pinfunction "2_2") (pintype "passive"))
      (node (ref "RP18") (pin "3") (pinfunction "3_3") (pintype "passive"))
      (node (ref "RP18") (pin "4") (pinfunction "4_4") (pintype "passive"))
      (node (ref "RP23") (pin "5") (pinfunction "5_5") (pintype "passive"))
      (node (ref "RP23") (pin "6") (pinfunction "6_6") (pintype "passive"))
      (node (ref "RP23") (pin "7") (pinfunction "7_7") (pintype "passive"))
      (node (ref "RP23") (pin "8") (pinfunction "8_8") (pintype "passive"))
      (node (ref "RP24") (pin "5") (pinfunction "5_5") (pintype "passive"))
      (node (ref "RP24") (pin "6") (pinfunction "6_6") (pintype "passive"))
      (node (ref "RP24") (pin "7") (pinfunction "7_7") (pintype "passive"))
      (node (ref "RP24") (pin "8") (pinfunction "8_8") (pintype "passive"))
      (node (ref "RP26") (pin "5") (pinfunction "5_5") (pintype "passive"))
      (node (ref "RP26") (pin "6") (pinfunction "6_6") (pintype "passive"))
      (node (ref "RP26") (pin "7") (pinfunction "7_7") (pintype "passive"))
      (node (ref "RP26") (pin "8") (pinfunction "8_8") (pintype "passive"))
      (node (ref "RP5") (pin "1") (pinfunction "1_1") (pintype "passive"))
      (node (ref "RP5") (pin "2") (pinfunction "2_2") (pintype "passive"))
      (node (ref "RP5") (pin "3") (pinfunction "3_3") (pintype "passive"))
      (node (ref "RP5") (pin "4") (pinfunction "4_4") (pintype "passive"))
      (node (ref "RP9") (pin "1") (pinfunction "1_1") (pintype "passive"))
      (node (ref "RP9") (pin "2") (pinfunction "2_2") (pintype "passive"))
      (node (ref "RP9") (pin "3") (pinfunction "3_3") (pintype "passive"))
      (node (ref "RP9") (pin "4") (pinfunction "4_4") (pintype "passive"))
      (node (ref "U17") (pin "7") (pinfunction "VEE_7") (pintype "passive"))
      (node (ref "U17") (pin "8") (pinfunction "GND_8") (pintype "passive"))
      (node (ref "U18") (pin "7") (pinfunction "VEE_7") (pintype "passive"))
      (node (ref "U18") (pin "8") (pinfunction "GND_8") (pintype "passive"))
      (node (ref "U20") (pin "7") (pinfunction "VEE_7") (pintype "passive"))
      (node (ref "U20") (pin "8") (pinfunction "GND_8") (pintype "passive"))
      (node (ref "U5") (pin "7") (pinfunction "VEE_7") (pintype "passive"))
      (node (ref "U5") (pin "8") (pinfunction "GND_8") (pintype "passive"))
    )
    (net (code "92") (name "Net-(C26-Pad1)") (class "Default")
      (node (ref "C26") (pin "1") (pinfunction "1_1") (pintype "passive"))
      (node (ref "R182") (pin "2") (pinfunction "2_2") (pintype "passive"))
      (node (ref "R44") (pin "1") (pinfunction "1_1") (pintype "passive"))
      (node (ref "RP6") (pin "1") (pinfunction "1_1") (pintype "passive"))
    )
    (net (code "93") (name "Net-(C27-Pad1)") (class "Default")
      (node (ref "C27") (pin "1") (pinfunction "1_1") (pintype "passive"))
      (node (ref "R183") (pin "2") (pinfunction "2_2") (pintype "passive"))
      (node (ref "R71") (pin "1") (pinfunction "1_1") (pintype "passive"))
      (node (ref "RP6") (pin "2") (pinfunction "2_2") (pintype "passive"))
    )
    (net (code "94") (name "Net-(C28-Pad1)") (class "Default")
      (node (ref "C28") (pin "1") (pinfunction "1_1") (pintype "passive"))
      (node (ref "R186") (pin "2") (pinfunction "2_2") (pintype "passive"))
      (node (ref "R91") (pin "1") (pinfunction "1_1") (pintype "passive"))
      (node (ref "RP6") (pin "3") (pinfunction "3_3") (pintype "passive"))
    )
    (net (code "95") (name "Net-(C29-Pad1)") (class "Default")
      (node (ref "C29") (pin "1") (pinfunction "1_1") (pintype "passive"))
      (node (ref "R187") (pin "2") (pinfunction "2_2") (pintype "passive"))
      (node (ref "R92") (pin "1") (pinfunction "1_1") (pintype "passive"))
      (node (ref "RP6") (pin "4") (pinfunction "4_4") (pintype "passive"))
    )
    (net (code "96") (name "Net-(C31-Pad1)") (class "Default")
      (node (ref "C31") (pin "1") (pinfunction "1_1") (pintype "passive"))
      (node (ref "R166") (pin "1") (pinfunction "1_1") (pintype "passive"))
      (node (ref "R191") (pin "2") (pinfunction "2_2") (pintype "passive"))
      (node (ref "RP8") (pin "2") (pinfunction "2_2") (pintype "passive"))
    )
    (net (code "97") (name "Net-(C33-Pad1)") (class "Default")
      (node (ref "C33") (pin "1") (pinfunction "1_1") (pintype "passive"))
      (node (ref "R113") (pin "1") (pinfunction "1_1") (pintype "passive"))
      (node (ref "R199") (pin "2") (pinfunction "2_2") (pintype "passive"))
      (node (ref "RP8") (pin "4") (pinfunction "4_4") (pintype "passive"))
    )
    (net (code "98") (name "Net-(C40-Pad1)") (class "Default")
      (node (ref "C40") (pin "1") (pinfunction "1_1") (pintype "passive"))
      (node (ref "R119") (pin "1") (pinfunction "1_1") (pintype "passive"))
      (node (ref "R206") (pin "2") (pinfunction "2_2") (pintype "passive"))
      (node (ref "RP15") (pin "4") (pinfunction "4_4") (pintype "passive"))
    )
    (net (code "99") (name "Net-(C41-Pad1)") (class "Default")
      (node (ref "C41") (pin "1") (pinfunction "1_1") (pintype "passive"))
      (node (ref "R120") (pin "1") (pinfunction "1_1") (pintype "passive"))
      (node (ref "R205") (pin "2") (pinfunction "2_2") (pintype "passive"))
      (node (ref "RP15") (pin "3") (pinfunction "3_3") (pintype "passive"))
    )
    (net (code "100") (name "Net-(C42-Pad1)") (class "Default")
      (node (ref "C42") (pin "1") (pinfunction "1_1") (pintype "passive"))
      (node (ref "R121") (pin "1") (pinfunction "1_1") (pintype "passive"))
      (node (ref "R203") (pin "2") (pinfunction "2_2") (pintype "passive"))
      (node (ref "RP15") (pin "2") (pinfunction "2_2") (pintype "passive"))
    )
    (net (code "101") (name "Net-(C43-Pad1)") (class "Default")
      (node (ref "C43") (pin "1") (pinfunction "1_1") (pintype "passive"))
      (node (ref "R122") (pin "1") (pinfunction "1_1") (pintype "passive"))
      (node (ref "R201") (pin "2") (pinfunction "2_2") (pintype "passive"))
      (node (ref "RP15") (pin "1") (pinfunction "1_1") (pintype "passive"))
    )
    (net (code "102") (name "Net-(C44-Pad1)") (class "Default")
      (node (ref "C44") (pin "1") (pinfunction "1_1") (pintype "passive"))
      (node (ref "R123") (pin "1") (pinfunction "1_1") (pintype "passive"))
      (node (ref "R214") (pin "2") (pinfunction "2_2") (pintype "passive"))
      (node (ref "RP17") (pin "4") (pinfunction "4_4") (pintype "passive"))
    )
    (net (code "103") (name "Net-(C45-Pad1)") (class "Default")
      (node (ref "C45") (pin "1") (pinfunction "1_1") (pintype "passive"))
      (node (ref "R124") (pin "1") (pinfunction "1_1") (pintype "passive"))
      (node (ref "R209") (pin "2") (pinfunction "2_2") (pintype "passive"))
      (node (ref "RP17") (pin "3") (pinfunction "3_3") (pintype "passive"))
    )
    (net (code "104") (name "Net-(C46-Pad1)") (class "Default")
      (node (ref "C46") (pin "1") (pinfunction "1_1") (pintype "passive"))
      (node (ref "R125") (pin "1") (pinfunction "1_1") (pintype "passive"))
      (node (ref "R208") (pin "2") (pinfunction "2_2") (pintype "passive"))
      (node (ref "RP17") (pin "2") (pinfunction "2_2") (pintype "passive"))
    )
    (net (code "105") (name "Net-(C47-Pad1)") (class "Default")
      (node (ref "C47") (pin "1") (pinfunction "1_1") (pintype "passive"))
      (node (ref "R126") (pin "1") (pinfunction "1_1") (pintype "passive"))
      (node (ref "R207") (pin "2") (pinfunction "2_2") (pintype "passive"))
      (node (ref "RP17") (pin "1") (pinfunction "1_1") (pintype "passive"))
    )
    (net (code "106") (name "Net-(C58-Pad1)") (class "Default")
      (node (ref "C58") (pin "1") (pinfunction "1_1") (pintype "passive"))
      (node (ref "R168") (pin "1") (pinfunction "1_1") (pintype "passive"))
      (node (ref "R63") (pin "2") (pinfunction "2_2") (pintype "passive"))
      (node (ref "RP21") (pin "8") (pinfunction "8_8") (pintype "passive"))
    )
    (net (code "107") (name "Net-(C59-Pad1)") (class "Default")
      (node (ref "C59") (pin "1") (pinfunction "1_1") (pintype "passive"))
      (node (ref "R61") (pin "2") (pinfunction "2_2") (pintype "passive"))
      (node (ref "R72") (pin "1") (pinfunction "1_1") (pintype "passive"))
      (node (ref "RP21") (pin "7") (pinfunction "7_7") (pintype "passive"))
    )
    (net (code "108") (name "Net-(C60-Pad1)") (class "Default")
      (node (ref "C60") (pin "1") (pinfunction "1_1") (pintype "passive"))
      (node (ref "R60") (pin "2") (pinfunction "2_2") (pintype "passive"))
      (node (ref "R77") (pin "1") (pinfunction "1_1") (pintype "passive"))
      (node (ref "RP21") (pin "6") (pinfunction "6_6") (pintype "passive"))
    )
    (net (code "109") (name "Net-(C61-Pad1)") (class "Default")
      (node (ref "C61") (pin "1") (pinfunction "1_1") (pintype "passive"))
      (node (ref "R59") (pin "2") (pinfunction "2_2") (pintype "passive"))
      (node (ref "R82") (pin "1") (pinfunction "1_1") (pintype "passive"))
      (node (ref "RP21") (pin "5") (pinfunction "5_5") (pintype "passive"))
    )
    (net (code "110") (name "Net-(C63-Pad1)") (class "Default")
      (node (ref "C63") (pin "1") (pinfunction "1_1") (pintype "passive"))
      (node (ref "R108") (pin "1") (pinfunction "1_1") (pintype "passive"))
      (node (ref "R68") (pin "2") (pinfunction "2_2") (pintype "passive"))
      (node (ref "RP22") (pin "3") (pinfunction "3_3") (pintype "passive"))
    )
    (net (code "111") (name "Net-(C64-Pad1)") (class "Default")
      (node (ref "C64") (pin "1") (pinfunction "1_1") (pintype "passive"))
      (node (ref "R51") (pin "1") (pinfunction "1_1") (pintype "passive"))
      (node (ref "R65") (pin "2") (pinfunction "2_2") (pintype "passive"))
      (node (ref "RP22") (pin "2") (pinfunction "2_2") (pintype "passive"))
    )
    (net (code "112") (name "Net-(C65-Pad1)") (class "Default")
      (node (ref "C65") (pin "1") (pinfunction "1_1") (pintype "passive"))
      (node (ref "R52") (pin "1") (pinfunction "1_1") (pintype "passive"))
      (node (ref "R64") (pin "2") (pinfunction "2_2") (pintype "passive"))
      (node (ref "RP22") (pin "1") (pinfunction "1_1") (pintype "passive"))
    )
    (net (code "113") (name "Net-(C68-Pad1)") (class "Default")
      (node (ref "C68") (pin "1") (pinfunction "1_1") (pintype "passive"))
      (node (ref "R80") (pin "1") (pinfunction "1_1") (pintype "passive"))
      (node (ref "R83") (pin "1") (pinfunction "1_1") (pintype "passive"))
      (node (ref "R85") (pin "2") (pinfunction "2_2") (pintype "passive"))
    )
    (net (code "114") (name "Net-(C85-Pad1)") (class "Default")
      (node (ref "C85") (pin "1") (pinfunction "1_1") (pintype "passive"))
      (node (ref "R109") (pin "1") (pinfunction "1_1") (pintype "passive"))
      (node (ref "R111") (pin "2") (pinfunction "2_2") (pintype "passive"))
      (node (ref "R127") (pin "1") (pinfunction "1_1") (pintype "passive"))
    )
    (net (code "115") (name "Net-(C91-Pad1)") (class "Default")
      (node (ref "C91") (pin "1") (pinfunction "1_1") (pintype "passive"))
      (node (ref "R190") (pin "2") (pinfunction "2_2") (pintype "passive"))
      (node (ref "R94") (pin "1") (pinfunction "1_1") (pintype "passive"))
      (node (ref "RP8") (pin "1") (pinfunction "1_1") (pintype "passive"))
    )
    (net (code "116") (name "Net-(C92-Pad1)") (class "Default")
      (node (ref "C92") (pin "1") (pinfunction "1_1") (pintype "passive"))
      (node (ref "R112") (pin "1") (pinfunction "1_1") (pintype "passive"))
      (node (ref "R198") (pin "2") (pinfunction "2_2") (pintype "passive"))
      (node (ref "RP8") (pin "3") (pinfunction "3_3") (pintype "passive"))
    )
    (net (code "117") (name "Net-(D4-A)") (class "Default")
      (node (ref "D4") (pin "1") (pinfunction "A_1") (pintype "passive"))
      (node (ref "Q14") (pin "2") (pinfunction "C_2") (pintype "passive"))
      (node (ref "R86") (pin "2") (pinfunction "2_2") (pintype "passive"))
    )
    (net (code "118") (name "Net-(D4-K)") (class "Default")
      (node (ref "C73") (pin "2") (pinfunction "2_2") (pintype "passive"))
      (node (ref "D4") (pin "2") (pinfunction "K_2") (pintype "passive"))
      (node (ref "R19") (pin "1") (pinfunction "1_1") (pintype "passive"))
      (node (ref "R8") (pin "1") (pinfunction "1_1") (pintype "passive"))
    )
    (net (code "119") (name "Net-(D12-K)") (class "Default")
      (node (ref "D12") (pin "2") (pinfunction "K_2") (pintype "passive"))
      (node (ref "Q2") (pin "1") (pinfunction "in_1") (pintype "input"))
    )
    (net (code "120") (name "Net-(D17-A)") (class "Default")
      (node (ref "D17") (pin "1") (pinfunction "A_1") (pintype "passive"))
      (node (ref "Q17") (pin "2") (pinfunction "C_2") (pintype "passive"))
      (node (ref "R132") (pin "2") (pinfunction "2_2") (pintype "passive"))
    )
    (net (code "121") (name "Net-(D17-K)") (class "Default")
      (node (ref "C74") (pin "1") (pinfunction "1_1") (pintype "passive"))
      (node (ref "D17") (pin "2") (pinfunction "K_2") (pintype "passive"))
      (node (ref "R20") (pin "1") (pinfunction "1_1") (pintype "passive"))
      (node (ref "R30") (pin "1") (pinfunction "1_1") (pintype "passive"))
    )
    (net (code "122") (name "Net-(D21-K)") (class "Default")
      (node (ref "D21") (pin "2") (pinfunction "K_2") (pintype "passive"))
      (node (ref "Q16") (pin "1") (pinfunction "in_1") (pintype "input"))
    )
    (net (code "123") (name "Net-(D33-K)") (class "Default")
      (node (ref "D33") (pin "2") (pinfunction "K_2") (pintype "passive"))
      (node (ref "Q13") (pin "1") (pinfunction "in_1") (pintype "input"))
    )
    (net (code "124") (name "Net-(Q2-out)") (class "Default")
      (node (ref "Q2") (pin "3") (pinfunction "out_3") (pintype "passive"))
      (node (ref "R16") (pin "1") (pinfunction "1_1") (pintype "passive"))
    )
    (net (code "125") (name "Net-(Q13-out)") (class "Default")
      (node (ref "Q13") (pin "3") (pinfunction "out_3") (pintype "passive"))
      (node (ref "R84") (pin "2") (pinfunction "2_2") (pintype "passive"))
    )
    (net (code "126") (name "Net-(Q14-B)") (class "Default")
      (node (ref "Q14") (pin "1") (pinfunction "B_1") (pintype "input"))
      (node (ref "R81") (pin "2") (pinfunction "2_2") (pintype "passive"))
      (node (ref "R84") (pin "1") (pinfunction "1_1") (pintype "passive"))
    )
    (net (code "127") (name "Net-(Q16-out)") (class "Default")
      (node (ref "Q16") (pin "3") (pinfunction "out_3") (pintype "passive"))
      (node (ref "R128") (pin "1") (pinfunction "1_1") (pintype "passive"))
    )
    (net (code "128") (name "Net-(Q17-B)") (class "Default")
      (node (ref "Q17") (pin "1") (pinfunction "B_1") (pintype "input"))
      (node (ref "R128") (pin "2") (pinfunction "2_2") (pintype "passive"))
      (node (ref "R57") (pin "2") (pinfunction "2_2") (pintype "passive"))
    )
    (net (code "129") (name "Net-(Q39-B)") (class "Default")
      (node (ref "Q39") (pin "1") (pinfunction "B_1") (pintype "input"))
      (node (ref "R110") (pin "1") (pinfunction "1_1") (pintype "passive"))
      (node (ref "R16") (pin "2") (pinfunction "2_2") (pintype "passive"))
    )
    (net (code "130") (name "Net-(R127-Pad2)") (class "Default")
      (node (ref "R127") (pin "2") (pinfunction "2_2") (pintype "passive"))
      (node (ref "R173") (pin "2") (pinfunction "2_2") (pintype "passive"))
    )
    (net (code "131") (name "Net-(U5-~{E})") (class "Default")
      (node (ref "R87") (pin "1") (pinfunction "1_1") (pintype "passive"))
      (node (ref "U5") (pin "6") (pinfunction "~{E}_6") (pintype "passive"))
    )
    (net (code "132") (name "Net-(U17-~{E})") (class "Default")
      (node (ref "R88") (pin "1") (pinfunction "1_1") (pintype "passive"))
      (node (ref "U17") (pin "6") (pinfunction "~{E}_6") (pintype "passive"))
    )
    (net (code "133") (name "Net-(U18-~{E})") (class "Default")
      (node (ref "R89") (pin "1") (pinfunction "1_1") (pintype "passive"))
      (node (ref "U18") (pin "6") (pinfunction "~{E}_6") (pintype "passive"))
    )
    (net (code "134") (name "Net-(U20-~{E})") (class "Default")
      (node (ref "R90") (pin "1") (pinfunction "1_1") (pintype "passive"))
      (node (ref "U20") (pin "6") (pinfunction "~{E}_6") (pintype "passive"))
    )
    (net (code "135") (name "V") (class "Default")
      (node (ref "Q39") (pin "3") (pinfunction "C_3") (pintype "passive"))
      (node (ref "R110") (pin "2") (pinfunction "2_2") (pintype "passive"))
      (node (ref "R123") (pin "2") (pinfunction "2_2") (pintype "passive"))
      (node (ref "R124") (pin "2") (pinfunction "2_2") (pintype "passive"))
      (node (ref "R199") (pin "1") (pinfunction "1_1") (pintype "passive"))
      (node (ref "R2") (pin "1") (pinfunction "1_1") (pintype "passive"))
      (node (ref "R44") (pin "2") (pinfunction "2_2") (pintype "passive"))
      (node (ref "R71") (pin "2") (pinfunction "2_2") (pintype "passive"))
    )
    (net (code "136") (name "V1") (class "Default")
      (node (ref "C1") (pin "1") (pinfunction "1_1") (pintype "passive"))
      (node (ref "Q39") (pin "2") (pinfunction "E_2") (pintype "passive"))
      (node (ref "R108") (pin "2") (pinfunction "2_2") (pintype "passive"))
      (node (ref "R109") (pin "2") (pinfunction "2_2") (pintype "passive"))
      (node (ref "R112") (pin "2") (pinfunction "2_2") (pintype "passive"))
      (node (ref "R113") (pin "2") (pinfunction "2_2") (pintype "passive"))
      (node (ref "R119") (pin "2") (pinfunction "2_2") (pintype "passive"))
      (node (ref "R120") (pin "2") (pinfunction "2_2") (pintype "passive"))
      (node (ref "R121") (pin "2") (pinfunction "2_2") (pintype "passive"))
      (node (ref "R122") (pin "2") (pinfunction "2_2") (pintype "passive"))
      (node (ref "R125") (pin "2") (pinfunction "2_2") (pintype "passive"))
      (node (ref "R126") (pin "2") (pinfunction "2_2") (pintype "passive"))
      (node (ref "R166") (pin "2") (pinfunction "2_2") (pintype "passive"))
      (node (ref "R168") (pin "2") (pinfunction "2_2") (pintype "passive"))
      (node (ref "R2") (pin "2") (pinfunction "2_2") (pintype "passive"))
      (node (ref "R51") (pin "2") (pinfunction "2_2") (pintype "passive"))
      (node (ref "R52") (pin "2") (pinfunction "2_2") (pintype "passive"))
      (node (ref "R72") (pin "2") (pinfunction "2_2") (pintype "passive"))
      (node (ref "R77") (pin "2") (pinfunction "2_2") (pintype "passive"))
      (node (ref "R80") (pin "2") (pinfunction "2_2") (pintype "passive"))
      (node (ref "R82") (pin "2") (pinfunction "2_2") (pintype "passive"))
      (node (ref "R91") (pin "2") (pinfunction "2_2") (pintype "passive"))
      (node (ref "R92") (pin "2") (pinfunction "2_2") (pintype "passive"))
      (node (ref "R94") (pin "2") (pinfunction "2_2") (pintype "passive"))
    )
    (net (code "137") (name "unconnected-(DZ4-Pad5)") (class "Default")
      (node (ref "DZ4") (pin "5") (pintype "passive+no_connect"))
    )
    (net (code "138") (name "unconnected-(DZ5-Pad5)") (class "Default")
      (node (ref "DZ5") (pin "5") (pintype "passive+no_connect"))
    )
    (net (code "139") (name "unconnected-(DZ7-Pad5)") (class "Default")
      (node (ref "DZ7") (pin "5") (pintype "passive"))
    )
    (net (code "140") (name "unconnected-(DZ8-Pad5)") (class "Default")
      (node (ref "DZ8") (pin "5") (pintype "passive"))
    )
    (net (code "141") (name "unconnected-(DZ10-Pad5)") (class "Default")
      (node (ref "DZ10") (pin "5") (pintype "passive"))
    )
    (net (code "142") (name "unconnected-(DZ11-Pad5)") (class "Default")
      (node (ref "DZ11") (pin "5") (pintype "passive"))
    )
    (net (code "143") (name "unconnected-(DZ11-Pad6)") (class "Default")
      (node (ref "DZ11") (pin "6") (pintype "passive"))
    )
    (net (code "144") (name "unconnected-(DZ13-Pad5)") (class "Default")
      (node (ref "DZ13") (pin "5") (pintype "passive"))
    )
    (net (code "145") (name "unconnected-(DZ14-Pad5)") (class "Default")
      (node (ref "DZ14") (pin "5") (pintype "passive"))
    )
    (net (code "146") (name "unconnected-(JA1-Pad1)") (class "Default")
      (node (ref "JA1") (pin "1") (pinfunction "1_1") (pintype "passive"))
    )
    (net (code "147") (name "unconnected-(JA1-Pad2)") (class "Default")
      (node (ref "JA1") (pin "2") (pinfunction "2_2") (pintype "passive"))
    )
    (net (code "148") (name "unconnected-(JA1-Pad15)") (class "Default")
      (node (ref "JA1") (pin "15") (pinfunction "15_15") (pintype "passive"))
    )
    (net (code "149") (name "unconnected-(JA1-Pad17)") (class "Default")
      (node (ref "JA1") (pin "17") (pinfunction "17_17") (pintype "passive"))
    )
    (net (code "150") (name "unconnected-(RP22-Pad4)") (class "Default")
      (node (ref "RP22") (pin "4") (pinfunction "4_4") (pintype "passive"))
    )
    (net (code "151") (name "unconnected-(RP22-Pad5)") (class "Default")
      (node (ref "RP22") (pin "5") (pinfunction "5_5") (pintype "passive"))
    )
    (net (code "152") (name "unconnected-(RP24-Pad1)") (class "Default")
      (node (ref "RP24") (pin "1") (pinfunction "1_1") (pintype "passive"))
    )
    (net (code "153") (name "unconnected-(U5-Y4-Pad1)") (class "Default")
      (node (ref "U5") (pin "1") (pinfunction "Y4_1") (pintype "passive"))
    )
    (net (code "154") (name "unconnected-(U5-Y6-Pad2)") (class "Default")
      (node (ref "U5") (pin "2") (pinfunction "Y6_2") (pintype "passive"))
    )
    (net (code "155") (name "unconnected-(U20-Y7-Pad4)") (class "Default")
      (node (ref "U20") (pin "4") (pinfunction "Y7_4") (pintype "passive"))
    )
  )
)
